# MINI_SAM_D51_003.net
KiCad netlist of a schematic drawn in EAGLE
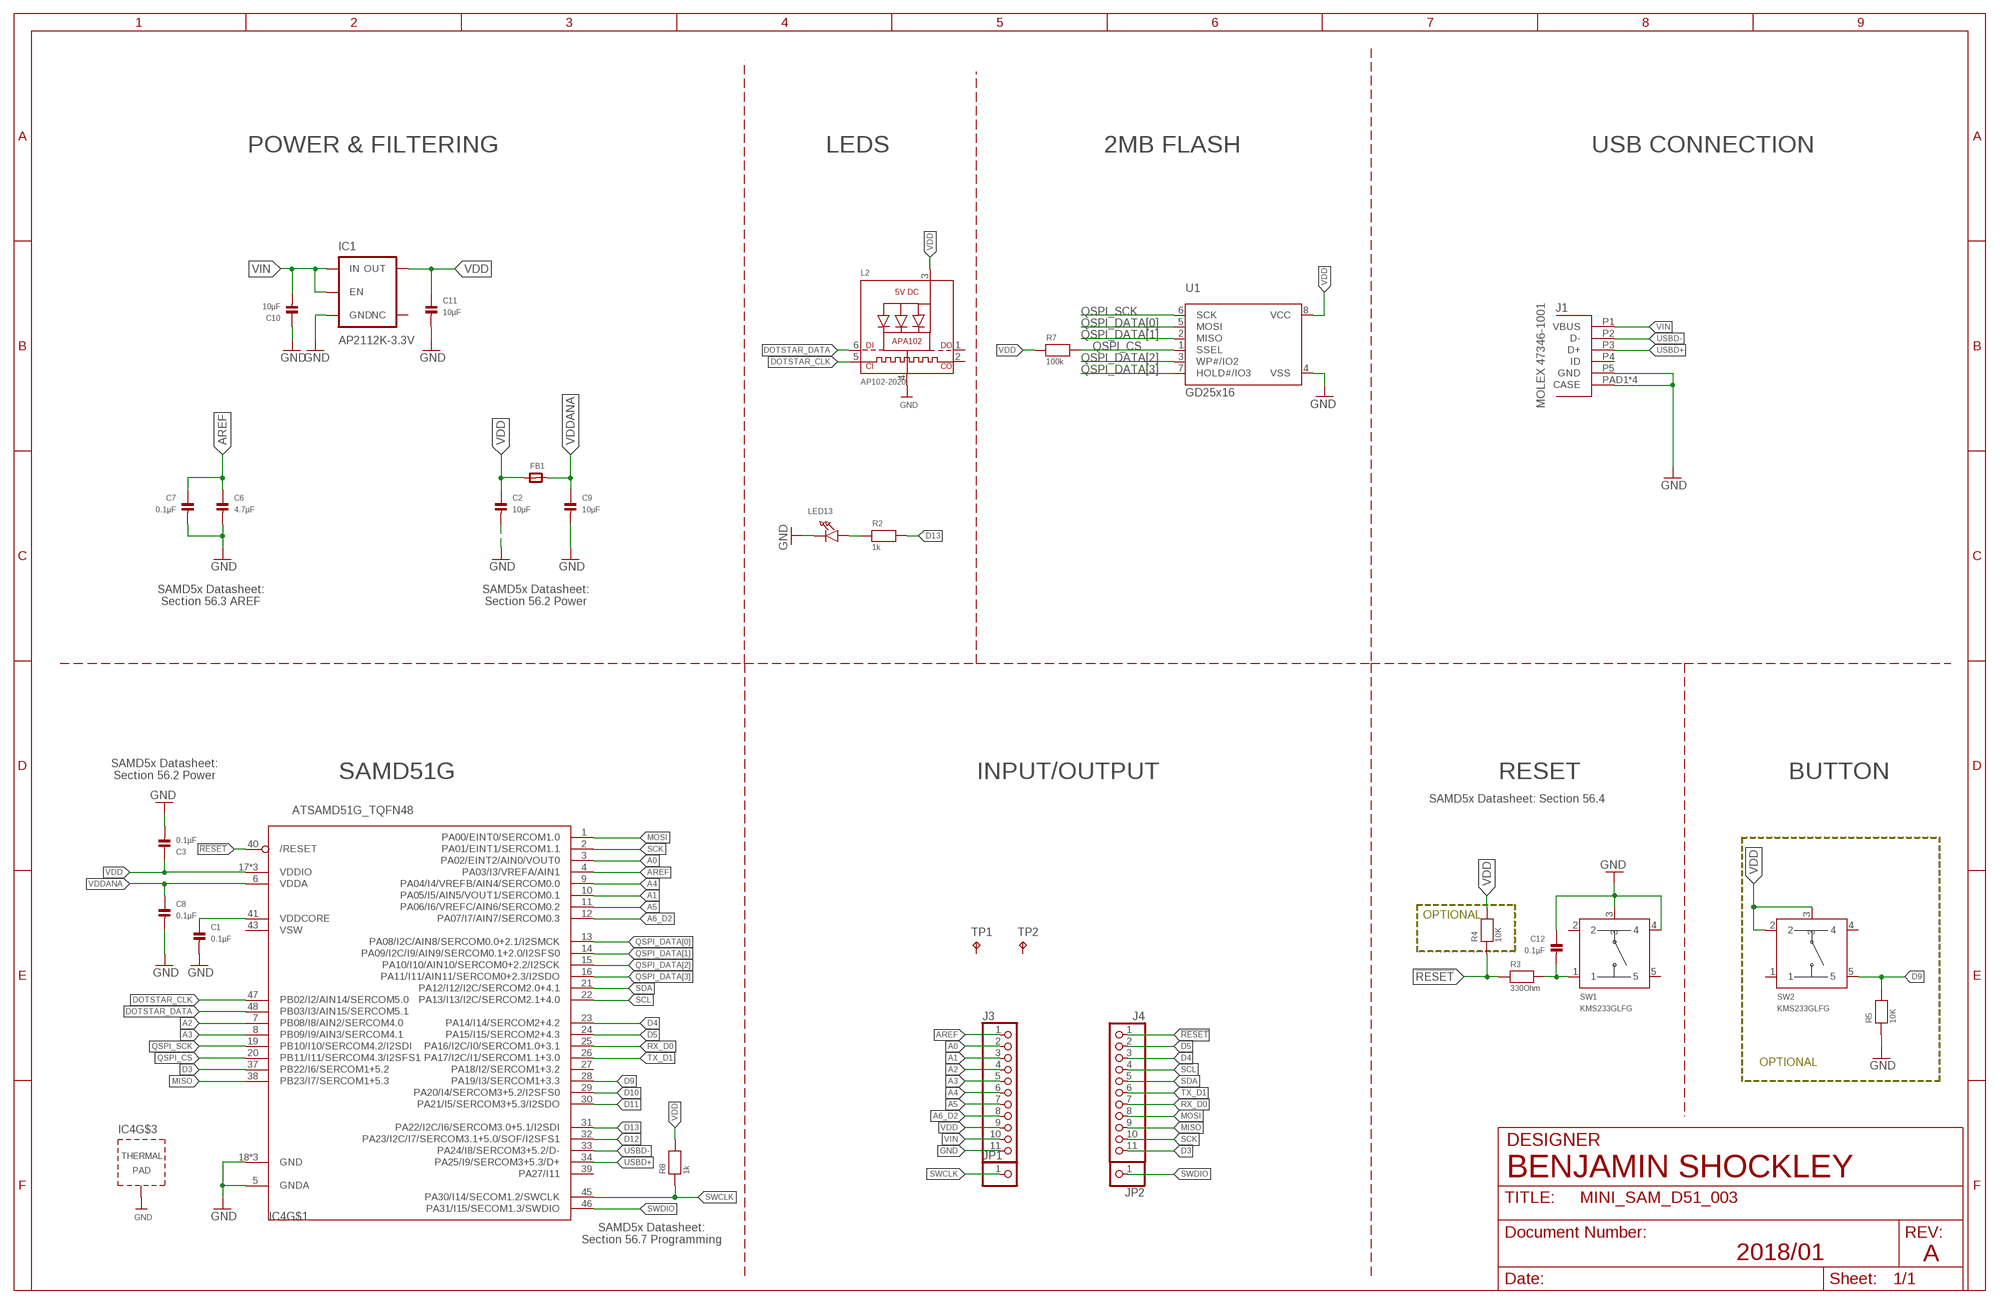
[diagram p0: schematic, sheet 1]

(export (version "E")
  (design (tool "Eeschema 10.0.6"))
  (components
    (comp (ref "C1")
      (value "0.1µF")
      (footprint "eagle-import:_0603MP")
      (libsource (lib "eagle-import") (part "CAP_CERAMIC_0603MP"))
    )
    (comp (ref "C2")
      (value "10µF")
      (footprint "eagle-import:_0603MP")
      (libsource (lib "eagle-import") (part "CAP_CERAMIC_0603MP"))
    )
    (comp (ref "C3")
      (value "0.1µF")
      (footprint "eagle-import:_0603MP")
      (libsource (lib "eagle-import") (part "CAP_CERAMIC_0603MP"))
    )
    (comp (ref "C6")
      (value "4.7µF")
      (footprint "eagle-import:_0603MP")
      (libsource (lib "eagle-import") (part "CAP_CERAMIC_0603MP"))
    )
    (comp (ref "C7")
      (value "0.1µF")
      (footprint "eagle-import:_0603MP")
      (libsource (lib "eagle-import") (part "CAP_CERAMIC_0603MP"))
    )
    (comp (ref "C8")
      (value "0.1µF")
      (footprint "eagle-import:_0603MP")
      (libsource (lib "eagle-import") (part "CAP_CERAMIC_0603MP"))
    )
    (comp (ref "C9")
      (value "10µF")
      (footprint "eagle-import:_0603MP")
      (libsource (lib "eagle-import") (part "CAP_CERAMIC_0603MP"))
    )
    (comp (ref "C10")
      (value "10µF")
      (footprint "eagle-import:_0603MP")
      (libsource (lib "eagle-import") (part "CAP_CERAMIC_0603MP"))
    )
    (comp (ref "C11")
      (value "10µF")
      (footprint "eagle-import:_0603MP")
      (libsource (lib "eagle-import") (part "CAP_CERAMIC_0603MP"))
    )
    (comp (ref "C12")
      (value "0.1µF")
      (footprint "eagle-import:_0603MP")
      (libsource (lib "eagle-import") (part "CAP_CERAMIC_0603MP"))
    )
    (comp (ref "FB1")
      (value "FERRITE_0603MP")
      (footprint "eagle-import:_0603MP")
      (libsource (lib "eagle-import") (part "FERRITE_0603MP"))
    )
    (comp (ref "IC1")
      (value "AP2112K-3.3V")
      (footprint "eagle-import:SOT23-5")
      (libsource (lib "eagle-import") (part "V_REG_AP2112K-3.3V"))
    )
    (comp (ref "IC4")
      (value "ATSAMD51G_TQFN48")
      (footprint "eagle-import:TQFN48_7MM")
      (libsource (lib "eagle-import") (part "ATSAMD51G_TQFN48"))
    )
    (comp (ref "J1")
      (value "MOLEX_47346-100147346")
      (footprint "eagle-import:MOLEX_47346-1001")
      (libsource (lib "eagle-import") (part "MOLEX_47346-100147346"))
    )
    (comp (ref "J3")
      (value "PINHD-1X111X11_SMT")
      (footprint "eagle-import:1X11_SMT")
      (libsource (lib "eagle-import") (part "PINHD-1X111X11_SMT"))
    )
    (comp (ref "J4")
      (value "PINHD-1X111X11_SMT")
      (footprint "eagle-import:1X11_SMT")
      (libsource (lib "eagle-import") (part "PINHD-1X111X11_SMT"))
    )
    (comp (ref "JP1")
      (value "HEADER-1X1ROUND")
      (footprint "eagle-import:1X01_ROUND")
      (libsource (lib "eagle-import") (part "HEADER-1X1ROUND"))
    )
    (comp (ref "JP2")
      (value "HEADER-1X1ROUND")
      (footprint "eagle-import:1X01_ROUND")
      (libsource (lib "eagle-import") (part "HEADER-1X1ROUND"))
    )
    (comp (ref "L2")
      (value "AP102-2020")
      (footprint "eagle-import:APA102_2020")
      (libsource (lib "eagle-import") (part "APA1022020"))
    )
    (comp (ref "LED13")
      (value "LED0603_NOOUTLINE")
      (footprint "eagle-import:CHIPLED_0603_NOOUTLINE")
      (libsource (lib "eagle-import") (part "LED0603_NOOUTLINE"))
    )
    (comp (ref "R2")
      (value "1k")
      (footprint "eagle-import:_0603MP")
      (libsource (lib "eagle-import") (part "RESISTOR_0603MP"))
    )
    (comp (ref "R3")
      (value "330Ohm")
      (footprint "eagle-import:_0603MP")
      (libsource (lib "eagle-import") (part "RESISTOR_0603MP"))
    )
    (comp (ref "R4")
      (value "10K")
      (footprint "eagle-import:_0603MP")
      (libsource (lib "eagle-import") (part "RESISTOR_0603MP"))
    )
    (comp (ref "R5")
      (value "10K")
      (footprint "eagle-import:_0603MP")
      (libsource (lib "eagle-import") (part "RESISTOR_0603MP"))
    )
    (comp (ref "R7")
      (value "100k")
      (footprint "eagle-import:_0603MP")
      (libsource (lib "eagle-import") (part "RESISTOR_0603MP"))
    )
    (comp (ref "R8")
      (value "1k")
      (footprint "eagle-import:_0603MP")
      (libsource (lib "eagle-import") (part "RESISTOR_0603MP"))
    )
    (comp (ref "SW1")
      (value "KMS233GLFG")
      (footprint "eagle-import:KMS_SWITCH")
      (libsource (lib "eagle-import") (part "KMS_SWITCHKMS"))
    )
    (comp (ref "SW2")
      (value "KMS233GLFG")
      (footprint "eagle-import:KMS_SWITCH")
      (libsource (lib "eagle-import") (part "KMS_SWITCHKMS"))
    )
    (comp (ref "TP1")
      (value "TPB1,27")
      (footprint "eagle-import:B1,27")
      (libsource (lib "eagle-import") (part "TPB1,27"))
    )
    (comp (ref "TP2")
      (value "TPB1,27")
      (footprint "eagle-import:B1,27")
      (libsource (lib "eagle-import") (part "TPB1,27"))
    )
    (comp (ref "U1")
      (value "GD25x16")
      (footprint "eagle-import:USON8")
      (libsource (lib "eagle-import") (part "SPIFLASH_8PINUX"))
    )
  )
  (nets
    (net (code "1") (name "/VSW") (class "Default")
      (node (ref "IC4") (pin "43") (pinfunction "VSW_43") (pintype "power_in"))
    )
    (net (code "2") (name "/~{RESET}") (class "Default")
      (node (ref "IC4") (pin "40") (pinfunction "/RESET_40") (pintype "bidirectional"))
      (node (ref "J4") (pin "1") (pinfunction "1_1") (pintype "passive"))
      (node (ref "R3") (pin "1") (pinfunction "1_1") (pintype "passive"))
      (node (ref "R4") (pin "1") (pinfunction "1_1") (pintype "passive"))
    )
    (net (code "3") (name "A0") (class "Default")
      (node (ref "IC4") (pin "3") (pinfunction "PA02/EINT2/AIN0/VOUT0_3") (pintype "bidirectional"))
      (node (ref "J3") (pin "2") (pinfunction "2_2") (pintype "passive"))
    )
    (net (code "4") (name "A1") (class "Default")
      (node (ref "IC4") (pin "10") (pinfunction "PA05/I5/AIN5/VOUT1/SERCOM0.1_10") (pintype "bidirectional"))
      (node (ref "J3") (pin "3") (pinfunction "3_3") (pintype "passive"))
    )
    (net (code "5") (name "A2") (class "Default")
      (node (ref "IC4") (pin "7") (pinfunction "PB08/I8/AIN2/SERCOM4.0_7") (pintype "bidirectional"))
      (node (ref "J3") (pin "4") (pinfunction "4_4") (pintype "passive"))
    )
    (net (code "6") (name "A3") (class "Default")
      (node (ref "IC4") (pin "8") (pinfunction "PB09/I9/AIN3/SERCOM4.1_8") (pintype "bidirectional"))
      (node (ref "J3") (pin "5") (pinfunction "5_5") (pintype "passive"))
    )
    (net (code "7") (name "A4") (class "Default")
      (node (ref "IC4") (pin "9") (pinfunction "PA04/I4/VREFB/AIN4/SERCOM0.0_9") (pintype "bidirectional"))
      (node (ref "J3") (pin "6") (pinfunction "6_6") (pintype "passive"))
    )
    (net (code "8") (name "A5") (class "Default")
      (node (ref "IC4") (pin "11") (pinfunction "PA06/I6/VREFC/AIN6/SERCOM0.2_11") (pintype "bidirectional"))
      (node (ref "J3") (pin "7") (pinfunction "7_7") (pintype "passive"))
    )
    (net (code "9") (name "A6_D2") (class "Default")
      (node (ref "IC4") (pin "12") (pinfunction "PA07/I7/AIN7/SERCOM0.3_12") (pintype "bidirectional"))
      (node (ref "J3") (pin "8") (pinfunction "8_8") (pintype "passive"))
    )
    (net (code "10") (name "AREF") (class "Default")
      (node (ref "C6") (pin "1") (pinfunction "P$1_1") (pintype "passive"))
      (node (ref "C7") (pin "1") (pinfunction "P$1_1") (pintype "passive"))
      (node (ref "IC4") (pin "4") (pinfunction "PA03/I3/VREFA/AIN1_4") (pintype "bidirectional"))
      (node (ref "J3") (pin "1") (pinfunction "1_1") (pintype "passive"))
    )
    (net (code "11") (name "D3") (class "Default")
      (node (ref "IC4") (pin "37") (pinfunction "PB22/I6/SERCOM1+5.2_37") (pintype "bidirectional"))
      (node (ref "J4") (pin "11") (pinfunction "11_11") (pintype "passive"))
    )
    (net (code "12") (name "D4") (class "Default")
      (node (ref "IC4") (pin "23") (pinfunction "PA14/I14/SERCOM2+4.2_23") (pintype "bidirectional"))
      (node (ref "J4") (pin "3") (pinfunction "3_3") (pintype "passive"))
    )
    (net (code "13") (name "D5") (class "Default")
      (node (ref "IC4") (pin "24") (pinfunction "PA15/I15/SERCOM2+4.3_24") (pintype "bidirectional"))
      (node (ref "J4") (pin "2") (pinfunction "2_2") (pintype "passive"))
    )
    (net (code "14") (name "D9") (class "Default")
      (node (ref "IC4") (pin "28") (pinfunction "PA19/I3/SERCOM1+3.3_28") (pintype "bidirectional"))
      (node (ref "R5") (pin "2") (pinfunction "2_2") (pintype "passive"))
      (node (ref "SW2") (pin "5") (pinfunction "5_5") (pintype "bidirectional"))
    )
    (net (code "15") (name "D10") (class "Default")
      (node (ref "IC4") (pin "29") (pinfunction "PA20/I4/SERCOM3+5.2/I2SFS0_29") (pintype "bidirectional"))
    )
    (net (code "16") (name "D11") (class "Default")
      (node (ref "IC4") (pin "30") (pinfunction "PA21/I5/SERCOM3+5.3/I2SDO_30") (pintype "bidirectional"))
    )
    (net (code "17") (name "D12") (class "Default")
      (node (ref "IC4") (pin "32") (pinfunction "PA23/I2C/I7/SERCOM3.1+5.0/SOF/I2SFS1_32") (pintype "bidirectional"))
    )
    (net (code "18") (name "D13") (class "Default")
      (node (ref "IC4") (pin "31") (pinfunction "PA22/I2C/I6/SERCOM3.0+5.1/I2SDI_31") (pintype "bidirectional"))
      (node (ref "R2") (pin "2") (pinfunction "2_2") (pintype "passive"))
    )
    (net (code "19") (name "DOTSTAR_CLK") (class "Default")
      (node (ref "IC4") (pin "47") (pinfunction "PB02/I2/AIN14/SERCOM5.0_47") (pintype "bidirectional"))
      (node (ref "L2") (pin "5") (pinfunction "CKI_5") (pintype "input"))
    )
    (net (code "20") (name "DOTSTAR_DATA") (class "Default")
      (node (ref "IC4") (pin "48") (pinfunction "PB03/I3/AIN15/SERCOM5.1_48") (pintype "bidirectional"))
      (node (ref "L2") (pin "6") (pinfunction "DI_6") (pintype "input"))
    )
    (net (code "21") (name "GND") (class "Default")
      (node (ref "C1") (pin "2") (pinfunction "P$2_2") (pintype "passive"))
      (node (ref "C10") (pin "1") (pinfunction "P$1_1") (pintype "passive"))
      (node (ref "C11") (pin "2") (pinfunction "P$2_2") (pintype "passive"))
      (node (ref "C12") (pin "1") (pinfunction "P$1_1") (pintype "passive"))
      (node (ref "C2") (pin "2") (pinfunction "P$2_2") (pintype "passive"))
      (node (ref "C3") (pin "2") (pinfunction "P$2_2") (pintype "passive"))
      (node (ref "C6") (pin "2") (pinfunction "P$2_2") (pintype "passive"))
      (node (ref "C7") (pin "2") (pinfunction "P$2_2") (pintype "passive"))
      (node (ref "C8") (pin "2") (pinfunction "P$2_2") (pintype "passive"))
      (node (ref "C9") (pin "2") (pinfunction "P$2_2") (pintype "passive"))
      (node (ref "IC1") (pin "2") (pinfunction "GND_2") (pintype "input"))
      (node (ref "IC4") (pin "18") (pinfunction "GND_18") (pintype "power_in"))
      (node (ref "IC4") (pin "35") (pinfunction "GND_35") (pintype "power_in"))
      (node (ref "IC4") (pin "42") (pinfunction "GND_42") (pintype "power_in"))
      (node (ref "IC4") (pin "5") (pinfunction "GNDA_5") (pintype "power_in"))
      (node (ref "IC4") (pin "THERMAL") (pinfunction "TP_THERMAL") (pintype "power_in"))
      (node (ref "J1") (pin "P5") (pinfunction "GND_P5") (pintype "power_in"))
      (node (ref "J1") (pin "PAD1") (pinfunction "CASE_PAD1") (pintype "bidirectional"))
      (node (ref "J1") (pin "PAD2") (pinfunction "CASE_PAD2") (pintype "bidirectional"))
      (node (ref "J1") (pin "PAD3") (pinfunction "CASE_PAD3") (pintype "bidirectional"))
      (node (ref "J1") (pin "PAD4") (pinfunction "CASE_PAD4") (pintype "bidirectional"))
      (node (ref "J3") (pin "11") (pinfunction "11_11") (pintype "passive"))
      (node (ref "L2") (pin "4") (pinfunction "GND_4") (pintype "power_in"))
      (node (ref "LED13") (pin "C") (pinfunction "C_C") (pintype "passive"))
      (node (ref "R5") (pin "1") (pinfunction "1_1") (pintype "passive"))
      (node (ref "SW1") (pin "3") (pinfunction "3_3") (pintype "bidirectional"))
      (node (ref "SW1") (pin "4") (pinfunction "4_4") (pintype "bidirectional"))
      (node (ref "U1") (pin "4") (pinfunction "VSS_4") (pintype "bidirectional"))
    )
    (net (code "22") (name "MISO") (class "Default")
      (node (ref "IC4") (pin "38") (pinfunction "PB23/I7/SERCOM1+5.3_38") (pintype "bidirectional"))
      (node (ref "J4") (pin "9") (pinfunction "9_9") (pintype "passive"))
    )
    (net (code "23") (name "MOSI") (class "Default")
      (node (ref "IC4") (pin "1") (pinfunction "PA00/EINT0/SERCOM1.0_1") (pintype "bidirectional"))
      (node (ref "J4") (pin "8") (pinfunction "8_8") (pintype "passive"))
    )
    (net (code "24") (name "Net-(C1-P$1)") (class "Default")
      (node (ref "C1") (pin "1") (pinfunction "P$1_1") (pintype "passive"))
      (node (ref "IC4") (pin "41") (pinfunction "VDDCORE_41") (pintype "power_in"))
    )
    (net (code "25") (name "Net-(C12-P$2)") (class "Default")
      (node (ref "C12") (pin "2") (pinfunction "P$2_2") (pintype "passive"))
      (node (ref "R3") (pin "2") (pinfunction "2_2") (pintype "passive"))
      (node (ref "SW1") (pin "1") (pinfunction "1_1") (pintype "bidirectional"))
    )
    (net (code "26") (name "Net-(LED13-PadA)") (class "Default")
      (node (ref "LED13") (pin "A") (pinfunction "A_A") (pintype "passive"))
      (node (ref "R2") (pin "1") (pinfunction "1_1") (pintype "passive"))
    )
    (net (code "27") (name "QSPI_CS") (class "Default")
      (node (ref "IC4") (pin "20") (pinfunction "PB11/I11/SERCOM4.3/I2SFS1_20") (pintype "bidirectional"))
      (node (ref "R7") (pin "2") (pinfunction "2_2") (pintype "passive"))
      (node (ref "U1") (pin "1") (pinfunction "SSEL_1") (pintype "bidirectional"))
    )
    (net (code "28") (name "QSPI_DATA[0]") (class "Default")
      (node (ref "IC4") (pin "13") (pinfunction "PA08/I2C/AIN8/SERCOM0.0+2.1/I2SMCK_13") (pintype "bidirectional"))
      (node (ref "U1") (pin "5") (pinfunction "MOSI_5") (pintype "bidirectional"))
    )
    (net (code "29") (name "QSPI_DATA[1]") (class "Default")
      (node (ref "IC4") (pin "14") (pinfunction "PA09/I2C/I9/AIN9/SERCOM0.1+2.0/I2SFS0_14") (pintype "bidirectional"))
      (node (ref "U1") (pin "2") (pinfunction "MISO_2") (pintype "bidirectional"))
    )
    (net (code "30") (name "QSPI_DATA[2]") (class "Default")
      (node (ref "IC4") (pin "15") (pinfunction "PA10/I10/AIN10/SERCOM0+2.2/I2SCK_15") (pintype "bidirectional"))
      (node (ref "U1") (pin "3") (pinfunction "WP#/IO2_3") (pintype "bidirectional"))
    )
    (net (code "31") (name "QSPI_DATA[3]") (class "Default")
      (node (ref "IC4") (pin "16") (pinfunction "PA11/I11/AIN11/SERCOM0+2.3/I2SDO_16") (pintype "bidirectional"))
      (node (ref "U1") (pin "7") (pinfunction "HOLD#/IO3_7") (pintype "bidirectional"))
    )
    (net (code "32") (name "QSPI_SCK") (class "Default")
      (node (ref "IC4") (pin "19") (pinfunction "PB10/I10/SERCOM4.2/I2SDI_19") (pintype "bidirectional"))
      (node (ref "U1") (pin "6") (pinfunction "SCK_6") (pintype "bidirectional"))
    )
    (net (code "33") (name "RX_D0") (class "Default")
      (node (ref "IC4") (pin "25") (pinfunction "PA16/I2C/I0/SERCOM1.0+3.1_25") (pintype "bidirectional"))
      (node (ref "J4") (pin "7") (pinfunction "7_7") (pintype "passive"))
    )
    (net (code "34") (name "SCK") (class "Default")
      (node (ref "IC4") (pin "2") (pinfunction "PA01/EINT1/SERCOM1.1_2") (pintype "bidirectional"))
      (node (ref "J4") (pin "10") (pinfunction "10_10") (pintype "passive"))
    )
    (net (code "35") (name "SCL") (class "Default")
      (node (ref "IC4") (pin "22") (pinfunction "PA13/I13/I2C/SERCOM2.1+4.0_22") (pintype "bidirectional"))
      (node (ref "J4") (pin "4") (pinfunction "4_4") (pintype "passive"))
    )
    (net (code "36") (name "SDA") (class "Default")
      (node (ref "IC4") (pin "21") (pinfunction "PA12/I12/I2C/SERCOM2.0+4.1_21") (pintype "bidirectional"))
      (node (ref "J4") (pin "5") (pinfunction "5_5") (pintype "passive"))
    )
    (net (code "37") (name "SWCLK") (class "Default")
      (node (ref "IC4") (pin "45") (pinfunction "PA30/I14/SECOM1.2/SWCLK_45") (pintype "bidirectional"))
      (node (ref "JP1") (pin "1") (pinfunction "1_1") (pintype "passive"))
      (node (ref "R8") (pin "1") (pinfunction "1_1") (pintype "passive"))
    )
    (net (code "38") (name "SWDIO") (class "Default")
      (node (ref "IC4") (pin "46") (pinfunction "PA31/I15/SECOM1.3/SWDIO_46") (pintype "bidirectional"))
      (node (ref "JP2") (pin "1") (pinfunction "1_1") (pintype "passive"))
    )
    (net (code "39") (name "TX_D1") (class "Default")
      (node (ref "IC4") (pin "26") (pinfunction "PA17/I2C/I1/SERCOM1.1+3.0_26") (pintype "bidirectional"))
      (node (ref "J4") (pin "6") (pinfunction "6_6") (pintype "passive"))
    )
    (net (code "40") (name "USBD+") (class "Default")
      (node (ref "IC4") (pin "34") (pinfunction "PA25/I9/SERCOM3+5.3/D+_34") (pintype "bidirectional"))
      (node (ref "J1") (pin "P3") (pinfunction "D+_P3") (pintype "bidirectional"))
    )
    (net (code "41") (name "USBD-") (class "Default")
      (node (ref "IC4") (pin "33") (pinfunction "PA24/I8/SERCOM3+5.2/D-_33") (pintype "bidirectional"))
      (node (ref "J1") (pin "P2") (pinfunction "D-_P2") (pintype "bidirectional"))
    )
    (net (code "42") (name "VDD") (class "Default")
      (node (ref "C11") (pin "1") (pinfunction "P$1_1") (pintype "passive"))
      (node (ref "C2") (pin "1") (pinfunction "P$1_1") (pintype "passive"))
      (node (ref "C3") (pin "1") (pinfunction "P$1_1") (pintype "passive"))
      (node (ref "FB1") (pin "1") (pinfunction "P$1_1") (pintype "passive"))
      (node (ref "IC1") (pin "5") (pinfunction "OUT_5") (pintype "passive"))
      (node (ref "IC4") (pin "17") (pinfunction "VDDIO_17") (pintype "power_in"))
      (node (ref "IC4") (pin "36") (pinfunction "VDDIO_36") (pintype "power_in"))
      (node (ref "IC4") (pin "44") (pinfunction "VDDIO_44") (pintype "power_in"))
      (node (ref "J3") (pin "9") (pinfunction "9_9") (pintype "passive"))
      (node (ref "L2") (pin "3") (pinfunction "VDD_3") (pintype "power_in"))
      (node (ref "R4") (pin "2") (pinfunction "2_2") (pintype "passive"))
      (node (ref "R7") (pin "1") (pinfunction "1_1") (pintype "passive"))
      (node (ref "R8") (pin "2") (pinfunction "2_2") (pintype "passive"))
      (node (ref "SW2") (pin "2") (pinfunction "2_2") (pintype "bidirectional"))
      (node (ref "SW2") (pin "3") (pinfunction "3_3") (pintype "bidirectional"))
      (node (ref "U1") (pin "8") (pinfunction "VCC_8") (pintype "bidirectional"))
    )
    (net (code "43") (name "VDDANA") (class "Default")
      (node (ref "C8") (pin "1") (pinfunction "P$1_1") (pintype "passive"))
      (node (ref "C9") (pin "1") (pinfunction "P$1_1") (pintype "passive"))
      (node (ref "FB1") (pin "2") (pinfunction "P$2_2") (pintype "passive"))
      (node (ref "IC4") (pin "6") (pinfunction "VDDA_6") (pintype "power_in"))
    )
    (net (code "44") (name "VIN") (class "Default")
      (node (ref "C10") (pin "2") (pinfunction "P$2_2") (pintype "passive"))
      (node (ref "IC1") (pin "1") (pinfunction "IN_1") (pintype "input"))
      (node (ref "IC1") (pin "3") (pinfunction "EN_3") (pintype "input"))
      (node (ref "J1") (pin "P1") (pinfunction "VBUS_P1") (pintype "power_in"))
      (node (ref "J3") (pin "10") (pinfunction "10_10") (pintype "passive"))
    )
    (net (code "45") (name "unconnected-(IC1-NC-Pad4)") (class "Default")
      (node (ref "IC1") (pin "4") (pinfunction "NC_4") (pintype "input"))
    )
    (net (code "46") (name "unconnected-(IC4A-PA18{slash}I2{slash}SERCOM1+3.2-Pad27)") (class "Default")
      (node (ref "IC4") (pin "27") (pinfunction "PA18/I2/SERCOM1+3.2_27") (pintype "bidirectional"))
    )
    (net (code "47") (name "unconnected-(IC4A-PA27{slash}I11-Pad39)") (class "Default")
      (node (ref "IC4") (pin "39") (pinfunction "PA27/I11_39") (pintype "bidirectional"))
    )
    (net (code "48") (name "unconnected-(J1-ID-PadP4)") (class "Default")
      (node (ref "J1") (pin "P4") (pinfunction "ID_P4") (pintype "bidirectional"))
    )
    (net (code "49") (name "unconnected-(L2-CKO-Pad2)") (class "Default")
      (node (ref "L2") (pin "2") (pinfunction "CKO_2") (pintype "output"))
    )
    (net (code "50") (name "unconnected-(L2-DO-Pad1)") (class "Default")
      (node (ref "L2") (pin "1") (pinfunction "DO_1") (pintype "output"))
    )
    (net (code "51") (name "unconnected-(SW1-Pad2)") (class "Default")
      (node (ref "SW1") (pin "2") (pinfunction "2_2") (pintype "bidirectional"))
    )
    (net (code "52") (name "unconnected-(SW1-Pad5)") (class "Default")
      (node (ref "SW1") (pin "5") (pinfunction "5_5") (pintype "bidirectional"))
    )
    (net (code "53") (name "unconnected-(SW2-Pad1)") (class "Default")
      (node (ref "SW2") (pin "1") (pinfunction "1_1") (pintype "bidirectional"))
    )
    (net (code "54") (name "unconnected-(SW2-Pad4)") (class "Default")
      (node (ref "SW2") (pin "4") (pinfunction "4_4") (pintype "bidirectional"))
    )
    (net (code "55") (name "unconnected-(TP1-PadTP)") (class "Default")
      (node (ref "TP1") (pin "TP") (pinfunction "TP_TP") (pintype "input"))
    )
    (net (code "56") (name "unconnected-(TP2-PadTP)") (class "Default")
      (node (ref "TP2") (pin "TP") (pinfunction "TP_TP") (pintype "input"))
    )
  )
)
